# EastPDA_New_Project_2020-11-07_16-59-03.net
KiCad netlist of a schematic drawn in EasyEDA
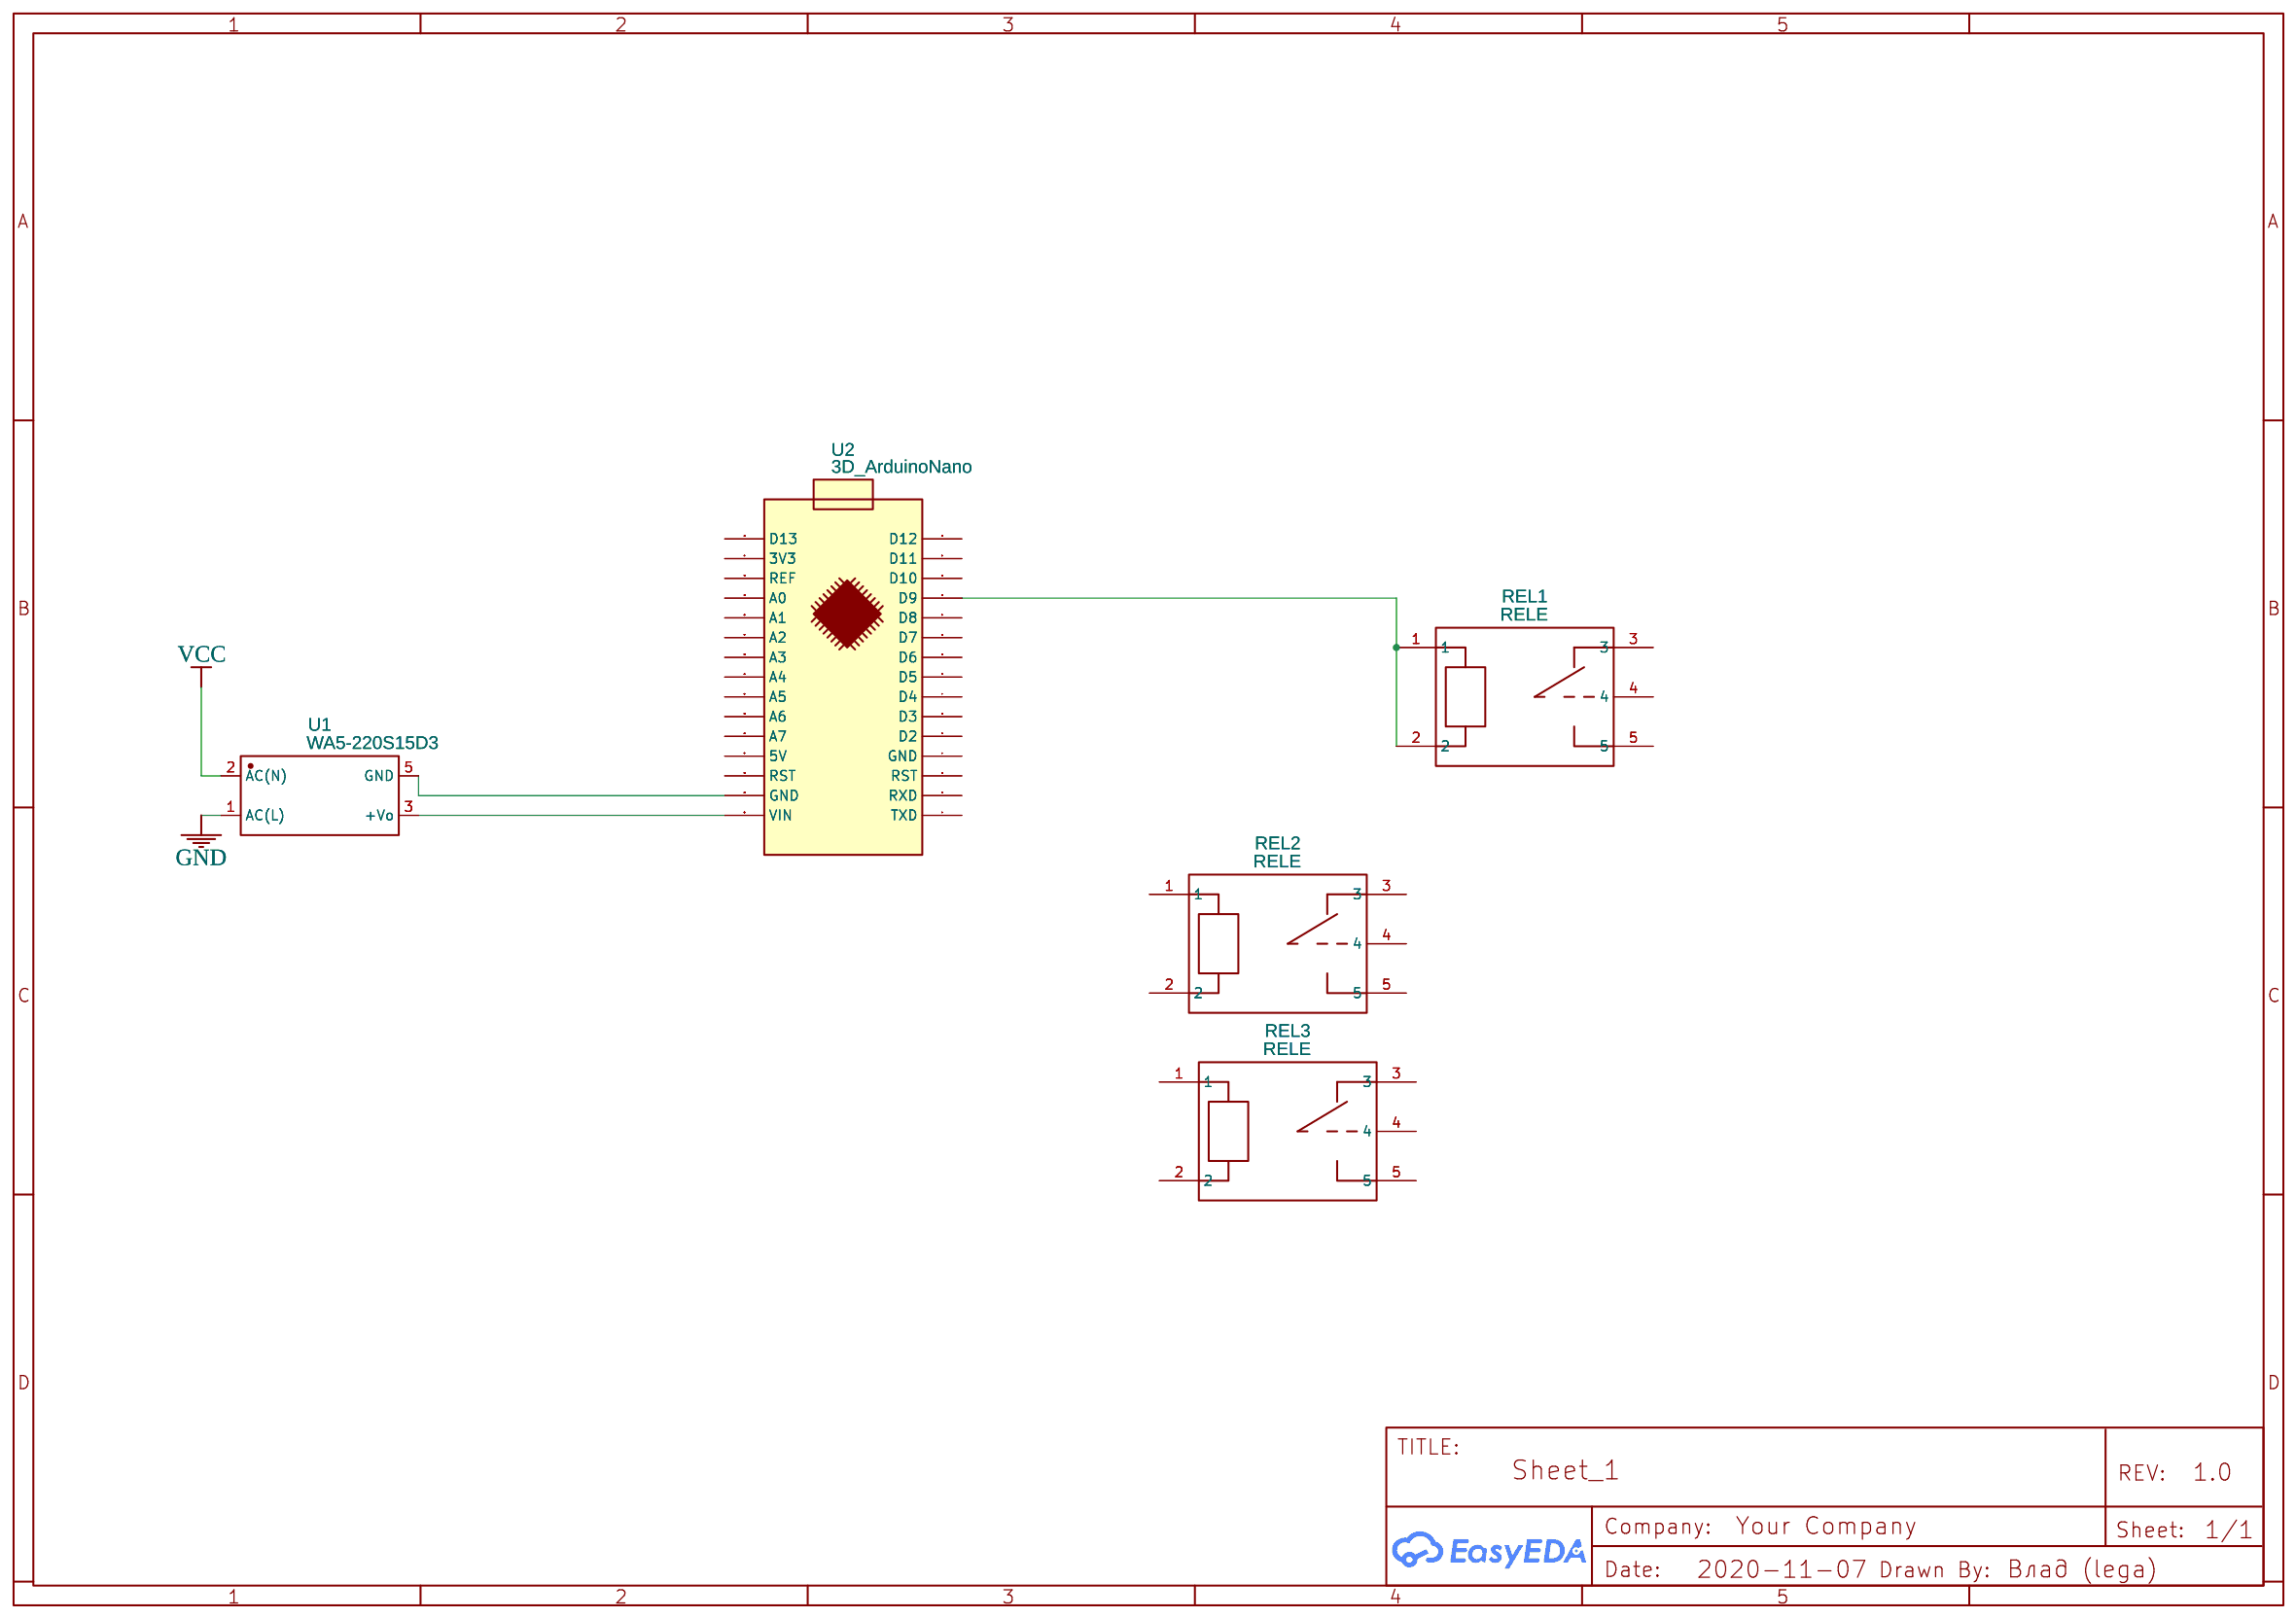
[diagram p0: schematic sheet]

(export (version "E")
  (design (tool "Eeschema 10.0.6"))
  (components
    (comp (ref "REL1") (value "RELE") (libsource (lib "") (part "RELE")))
    (comp (ref "REL2") (value "RELE") (libsource (lib "") (part "RELE")))
    (comp (ref "REL3") (value "RELE") (libsource (lib "") (part "RELE")))
    (comp (ref "U1")
      (value "WA5-220S15D3")
      (fields (field (name "BOM_Supplier Part") "C135525"))
      (libsource (lib "") (part "WA5-220S15D3"))
    )
    (comp (ref "U2")
      (value "3D_ArduinoNano")
      (fields (field (name "BOM_Manufacturer Part") "ArduinoNano"))
      (libsource (lib "") (part "3D_ArduinoNano"))
    )
  )
  (nets
    (net (code "1") (name "GND") (class "Default")
      (node (ref "U1") (pin "1") (pinfunction "AC(L)_1") (pintype "unspecified"))
    )
    (net (code "2") (name "Net-(U1-+Vo)") (class "Default")
      (node (ref "U1") (pin "3") (pinfunction "+Vo_3") (pintype "unspecified"))
      (node (ref "U2") (pin "30") (pinfunction "VIN_30") (pintype "unspecified"))
    )
    (net (code "3") (name "Net-(U1-GND)") (class "Default")
      (node (ref "U1") (pin "5") (pinfunction "GND_5") (pintype "unspecified"))
      (node (ref "U2") (pin "29") (pinfunction "GND_29") (pintype "unspecified"))
    )
    (net (code "4") (name "Net-(U2-D9)") (class "Default")
      (node (ref "REL1") (pin "1") (pinfunction "1_1") (pintype "input"))
      (node (ref "REL1") (pin "2") (pinfunction "2_2") (pintype "output"))
      (node (ref "U2") (pin "12") (pinfunction "D9_12") (pintype "unspecified"))
    )
    (net (code "5") (name "VCC") (class "Default")
      (node (ref "U1") (pin "2") (pinfunction "AC(N)_2") (pintype "unspecified"))
    )
    (net (code "6") (name "unconnected-(REL1-Pad3)") (class "Default")
      (node (ref "REL1") (pin "3") (pinfunction "3_3") (pintype "output"))
    )
    (net (code "7") (name "unconnected-(REL1-Pad4)") (class "Default")
      (node (ref "REL1") (pin "4") (pinfunction "4_4") (pintype "input"))
    )
    (net (code "8") (name "unconnected-(REL1-Pad5)") (class "Default")
      (node (ref "REL1") (pin "5") (pinfunction "5_5") (pintype "output"))
    )
    (net (code "9") (name "unconnected-(REL2-Pad1)") (class "Default")
      (node (ref "REL2") (pin "1") (pinfunction "1_1") (pintype "input"))
    )
    (net (code "10") (name "unconnected-(REL2-Pad2)") (class "Default")
      (node (ref "REL2") (pin "2") (pinfunction "2_2") (pintype "output"))
    )
    (net (code "11") (name "unconnected-(REL2-Pad3)") (class "Default")
      (node (ref "REL2") (pin "3") (pinfunction "3_3") (pintype "output"))
    )
    (net (code "12") (name "unconnected-(REL2-Pad4)") (class "Default")
      (node (ref "REL2") (pin "4") (pinfunction "4_4") (pintype "input"))
    )
    (net (code "13") (name "unconnected-(REL2-Pad5)") (class "Default")
      (node (ref "REL2") (pin "5") (pinfunction "5_5") (pintype "output"))
    )
    (net (code "14") (name "unconnected-(REL3-Pad1)") (class "Default")
      (node (ref "REL3") (pin "1") (pinfunction "1_1") (pintype "input"))
    )
    (net (code "15") (name "unconnected-(REL3-Pad2)") (class "Default")
      (node (ref "REL3") (pin "2") (pinfunction "2_2") (pintype "output"))
    )
    (net (code "16") (name "unconnected-(REL3-Pad3)") (class "Default")
      (node (ref "REL3") (pin "3") (pinfunction "3_3") (pintype "output"))
    )
    (net (code "17") (name "unconnected-(REL3-Pad4)") (class "Default")
      (node (ref "REL3") (pin "4") (pinfunction "4_4") (pintype "input"))
    )
    (net (code "18") (name "unconnected-(REL3-Pad5)") (class "Default")
      (node (ref "REL3") (pin "5") (pinfunction "5_5") (pintype "output"))
    )
    (net (code "19") (name "unconnected-(U2-3V3-Pad17)") (class "Default")
      (node (ref "U2") (pin "17") (pinfunction "3V3_17") (pintype "unspecified"))
    )
    (net (code "20") (name "unconnected-(U2-5V-Pad27)") (class "Default")
      (node (ref "U2") (pin "27") (pinfunction "5V_27") (pintype "unspecified"))
    )
    (net (code "21") (name "unconnected-(U2-A0-Pad19)") (class "Default")
      (node (ref "U2") (pin "19") (pinfunction "A0_19") (pintype "unspecified"))
    )
    (net (code "22") (name "unconnected-(U2-A1-Pad20)") (class "Default")
      (node (ref "U2") (pin "20") (pinfunction "A1_20") (pintype "unspecified"))
    )
    (net (code "23") (name "unconnected-(U2-A2-Pad21)") (class "Default")
      (node (ref "U2") (pin "21") (pinfunction "A2_21") (pintype "unspecified"))
    )
    (net (code "24") (name "unconnected-(U2-A3-Pad22)") (class "Default")
      (node (ref "U2") (pin "22") (pinfunction "A3_22") (pintype "unspecified"))
    )
    (net (code "25") (name "unconnected-(U2-A4-Pad23)") (class "Default")
      (node (ref "U2") (pin "23") (pinfunction "A4_23") (pintype "unspecified"))
    )
    (net (code "26") (name "unconnected-(U2-A5-Pad24)") (class "Default")
      (node (ref "U2") (pin "24") (pinfunction "A5_24") (pintype "unspecified"))
    )
    (net (code "27") (name "unconnected-(U2-A6-Pad25)") (class "Default")
      (node (ref "U2") (pin "25") (pinfunction "A6_25") (pintype "unspecified"))
    )
    (net (code "28") (name "unconnected-(U2-A7-Pad26)") (class "Default")
      (node (ref "U2") (pin "26") (pinfunction "A7_26") (pintype "unspecified"))
    )
    (net (code "29") (name "unconnected-(U2-D2-Pad5)") (class "Default")
      (node (ref "U2") (pin "5") (pinfunction "D2_5") (pintype "unspecified"))
    )
    (net (code "30") (name "unconnected-(U2-D3-Pad6)") (class "Default")
      (node (ref "U2") (pin "6") (pinfunction "D3_6") (pintype "unspecified"))
    )
    (net (code "31") (name "unconnected-(U2-D4-Pad7)") (class "Default")
      (node (ref "U2") (pin "7") (pinfunction "D4_7") (pintype "unspecified"))
    )
    (net (code "32") (name "unconnected-(U2-D5-Pad8)") (class "Default")
      (node (ref "U2") (pin "8") (pinfunction "D5_8") (pintype "unspecified"))
    )
    (net (code "33") (name "unconnected-(U2-D6-Pad9)") (class "Default")
      (node (ref "U2") (pin "9") (pinfunction "D6_9") (pintype "unspecified"))
    )
    (net (code "34") (name "unconnected-(U2-D7-Pad10)") (class "Default")
      (node (ref "U2") (pin "10") (pinfunction "D7_10") (pintype "unspecified"))
    )
    (net (code "35") (name "unconnected-(U2-D8-Pad11)") (class "Default")
      (node (ref "U2") (pin "11") (pinfunction "D8_11") (pintype "unspecified"))
    )
    (net (code "36") (name "unconnected-(U2-D10-Pad13)") (class "Default")
      (node (ref "U2") (pin "13") (pinfunction "D10_13") (pintype "unspecified"))
    )
    (net (code "37") (name "unconnected-(U2-D11-Pad14)") (class "Default")
      (node (ref "U2") (pin "14") (pinfunction "D11_14") (pintype "unspecified"))
    )
    (net (code "38") (name "unconnected-(U2-D12-Pad15)") (class "Default")
      (node (ref "U2") (pin "15") (pinfunction "D12_15") (pintype "unspecified"))
    )
    (net (code "39") (name "unconnected-(U2-D13-Pad16)") (class "Default")
      (node (ref "U2") (pin "16") (pinfunction "D13_16") (pintype "unspecified"))
    )
    (net (code "40") (name "unconnected-(U2-GND-Pad4)") (class "Default")
      (node (ref "U2") (pin "4") (pinfunction "GND_4") (pintype "unspecified"))
    )
    (net (code "41") (name "unconnected-(U2-REF-Pad18)") (class "Default")
      (node (ref "U2") (pin "18") (pinfunction "REF_18") (pintype "unspecified"))
    )
    (net (code "42") (name "unconnected-(U2-RST-Pad3)") (class "Default")
      (node (ref "U2") (pin "3") (pinfunction "RST_3") (pintype "unspecified"))
    )
    (net (code "43") (name "unconnected-(U2-RST-Pad28)") (class "Default")
      (node (ref "U2") (pin "28") (pinfunction "RST_28") (pintype "unspecified"))
    )
    (net (code "44") (name "unconnected-(U2-RXD-Pad2)") (class "Default")
      (node (ref "U2") (pin "2") (pinfunction "RXD_2") (pintype "unspecified"))
    )
    (net (code "45") (name "unconnected-(U2-TXD-Pad1)") (class "Default")
      (node (ref "U2") (pin "1") (pinfunction "TXD_1") (pintype "unspecified"))
    )
  )
)
